# EthernetPHY.net
KiCad netlist of a schematic drawn in Altium Designer
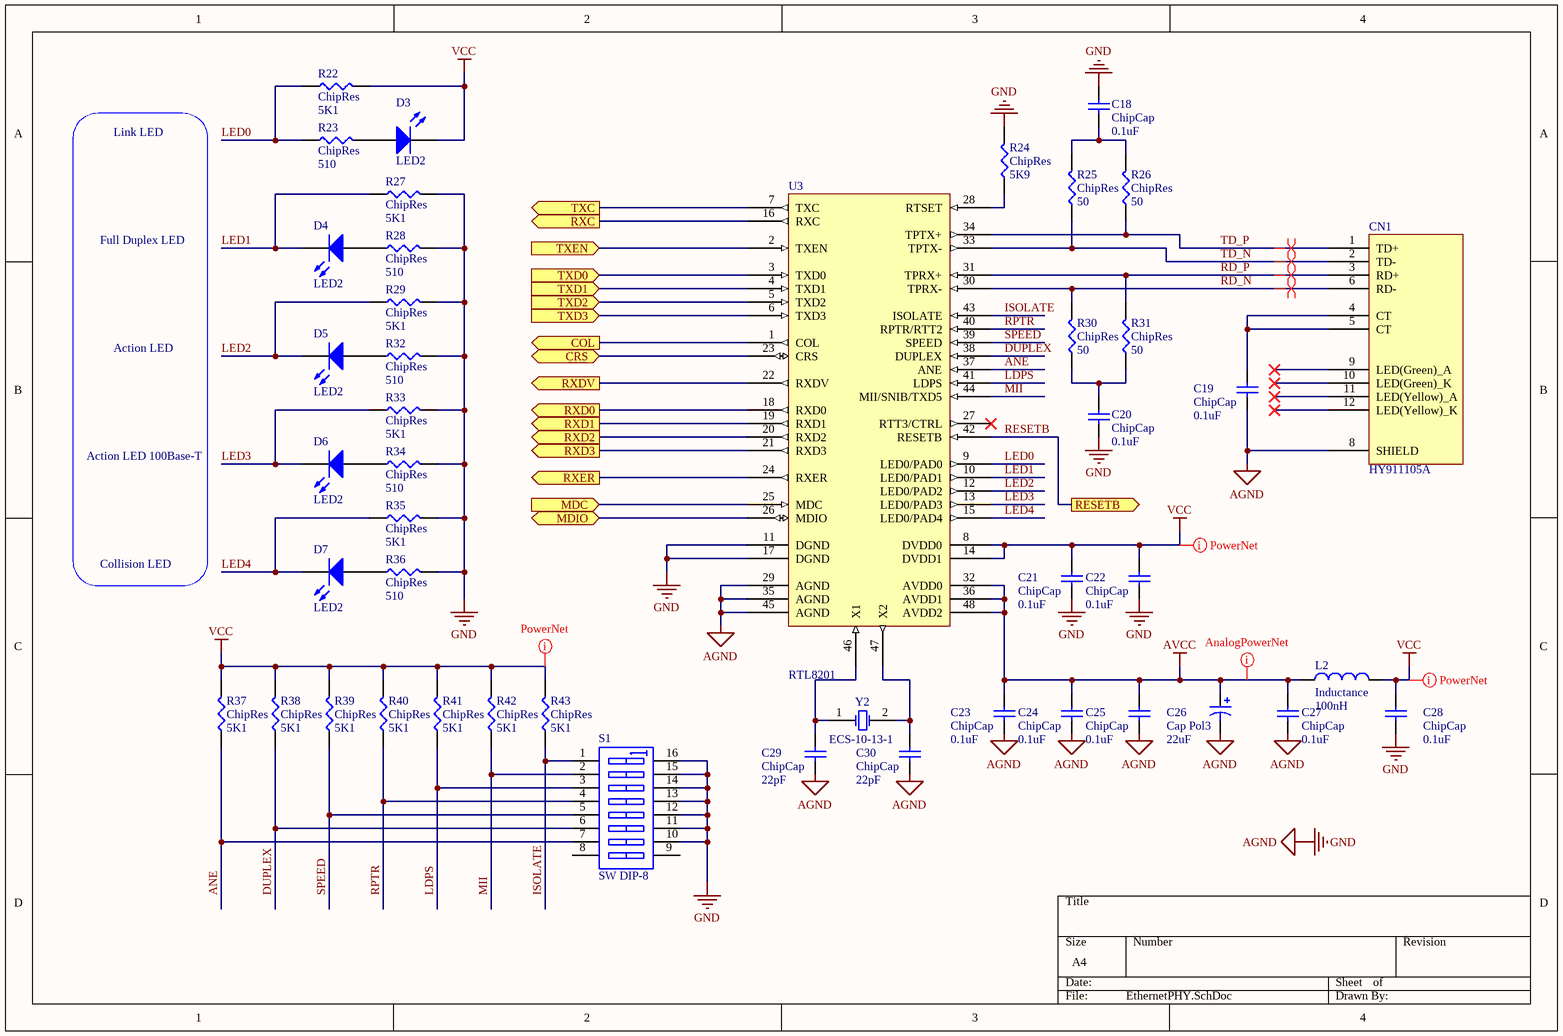
[diagram p0: EthernetPHY.SchDoc]

(export (version "E")
  (design (tool "Eeschema 10.0.6"))
  (components
    (comp (ref "C18")
      (value "ChipCap")
      (footprint "CAP0805")
      (description "Capacitor")
      (fields (field (name "ALTIUM_VALUE") "0.1uF") (field (name "PUBLISHER") "Altium Limited"))
      (libsource (lib "Common Devices") (part "ChipCap"))
    )
    (comp (ref "C19")
      (value "ChipCap")
      (footprint "CAP0805")
      (description "Capacitor")
      (fields (field (name "ALTIUM_VALUE") "0.1uF") (field (name "PUBLISHER") "Altium Limited"))
      (libsource (lib "Common Devices") (part "ChipCap"))
    )
    (comp (ref "C20")
      (value "ChipCap")
      (footprint "CAP0805")
      (description "Capacitor")
      (fields (field (name "ALTIUM_VALUE") "0.1uF") (field (name "PUBLISHER") "Altium Limited"))
      (libsource (lib "Common Devices") (part "ChipCap"))
    )
    (comp (ref "C21")
      (value "ChipCap")
      (footprint "CAP0805")
      (description "Capacitor")
      (fields (field (name "ALTIUM_VALUE") "0.1uF") (field (name "PUBLISHER") "Altium Limited"))
      (libsource (lib "Common Devices") (part "ChipCap"))
    )
    (comp (ref "C22")
      (value "ChipCap")
      (footprint "CAP0805")
      (description "Capacitor")
      (fields (field (name "ALTIUM_VALUE") "0.1uF") (field (name "PUBLISHER") "Altium Limited"))
      (libsource (lib "Common Devices") (part "ChipCap"))
    )
    (comp (ref "C23")
      (value "ChipCap")
      (footprint "CAP0805")
      (description "Capacitor")
      (fields (field (name "ALTIUM_VALUE") "0.1uF") (field (name "PUBLISHER") "Altium Limited"))
      (libsource (lib "Common Devices") (part "ChipCap"))
    )
    (comp (ref "C24")
      (value "ChipCap")
      (footprint "CAP0805")
      (description "Capacitor")
      (fields (field (name "ALTIUM_VALUE") "0.1uF") (field (name "PUBLISHER") "Altium Limited"))
      (libsource (lib "Common Devices") (part "ChipCap"))
    )
    (comp (ref "C25")
      (value "ChipCap")
      (footprint "CAP0805")
      (description "Capacitor")
      (fields (field (name "ALTIUM_VALUE") "0.1uF") (field (name "PUBLISHER") "Altium Limited"))
      (libsource (lib "Common Devices") (part "ChipCap"))
    )
    (comp (ref "C26")
      (value "Cap Pol3")
      (footprint "1812")
      (description "Polarized Capacitor (Surface Mount)")
      (fields (field (name "ALTIUM_VALUE") "22uF") (field (name "PUBLISHER") "Altium Limited"))
      (libsource (lib "Miscellaneous Devices") (part "Cap Pol3"))
    )
    (comp (ref "C27")
      (value "ChipCap")
      (footprint "CAP0805")
      (description "Capacitor")
      (fields (field (name "ALTIUM_VALUE") "0.1uF") (field (name "PUBLISHER") "Altium Limited"))
      (libsource (lib "Common Devices") (part "ChipCap"))
    )
    (comp (ref "C28")
      (value "ChipCap")
      (footprint "CAP0805")
      (description "Capacitor")
      (fields (field (name "ALTIUM_VALUE") "0.1uF") (field (name "PUBLISHER") "Altium Limited"))
      (libsource (lib "Common Devices") (part "ChipCap"))
    )
    (comp (ref "C29")
      (value "ChipCap")
      (footprint "CAP0805")
      (description "Capacitor")
      (fields (field (name "ALTIUM_VALUE") "22pF") (field (name "PUBLISHER") "Altium Limited"))
      (libsource (lib "Common Devices") (part "ChipCap"))
    )
    (comp (ref "C30")
      (value "ChipCap")
      (footprint "CAP0805")
      (description "Capacitor")
      (fields (field (name "ALTIUM_VALUE") "22pF") (field (name "PUBLISHER") "Altium Limited"))
      (libsource (lib "Common Devices") (part "ChipCap"))
    )
    (comp (ref "CN1")
      (value "HY911105A")
      (footprint "HR911105A")
      (libsource (lib "Connectors") (part "HY911105A"))
    )
    (comp (ref "D3")
      (value "LED2")
      (footprint "3.2X1.6X1.1")
      (description "Typical RED, GREEN, YELLOW, AMBER GaAs LED")
      (fields (field (name "PUBLISHER") "Altium Limited"))
      (libsource (lib "Miscellaneous Devices") (part "LED2"))
    )
    (comp (ref "D4")
      (value "LED2")
      (footprint "3.2X1.6X1.1")
      (description "Typical RED, GREEN, YELLOW, AMBER GaAs LED")
      (fields (field (name "PUBLISHER") "Altium Limited"))
      (libsource (lib "Miscellaneous Devices") (part "LED2"))
    )
    (comp (ref "D5")
      (value "LED2")
      (footprint "3.2X1.6X1.1")
      (description "Typical RED, GREEN, YELLOW, AMBER GaAs LED")
      (fields (field (name "PUBLISHER") "Altium Limited"))
      (libsource (lib "Miscellaneous Devices") (part "LED2"))
    )
    (comp (ref "D6")
      (value "LED2")
      (footprint "3.2X1.6X1.1")
      (description "Typical RED, GREEN, YELLOW, AMBER GaAs LED")
      (fields (field (name "PUBLISHER") "Altium Limited"))
      (libsource (lib "Miscellaneous Devices") (part "LED2"))
    )
    (comp (ref "D7")
      (value "LED2")
      (footprint "3.2X1.6X1.1")
      (description "Typical RED, GREEN, YELLOW, AMBER GaAs LED")
      (fields (field (name "PUBLISHER") "Altium Limited"))
      (libsource (lib "Miscellaneous Devices") (part "LED2"))
    )
    (comp (ref "L2")
      (value "Inductance")
      (footprint "CM32")
      (fields (field (name "ALTIUM_VALUE") "100nH"))
      (libsource (lib "Common Devices") (part "ChipInductance"))
    )
    (comp (ref "R22")
      (value "ChipRes")
      (footprint "RES0805")
      (description "Chip resistor")
      (fields (field (name "ALTIUM_VALUE") "5K1"))
      (libsource (lib "Common Devices") (part "ChipRes"))
    )
    (comp (ref "R23")
      (value "ChipRes")
      (footprint "RES0805")
      (description "Chip resistor")
      (fields (field (name "ALTIUM_VALUE") "510"))
      (libsource (lib "Common Devices") (part "ChipRes"))
    )
    (comp (ref "R24")
      (value "ChipRes")
      (footprint "RES0805")
      (description "Chip resistor")
      (fields (field (name "ALTIUM_VALUE") "5K9"))
      (libsource (lib "Common Devices") (part "ChipRes"))
    )
    (comp (ref "R25")
      (value "ChipRes")
      (footprint "RES0805")
      (description "Chip resistor")
      (fields (field (name "ALTIUM_VALUE") "50"))
      (libsource (lib "Common Devices") (part "ChipRes"))
    )
    (comp (ref "R26")
      (value "ChipRes")
      (footprint "RES0805")
      (description "Chip resistor")
      (fields (field (name "ALTIUM_VALUE") "50"))
      (libsource (lib "Common Devices") (part "ChipRes"))
    )
    (comp (ref "R27")
      (value "ChipRes")
      (footprint "RES0805")
      (description "Chip resistor")
      (fields (field (name "ALTIUM_VALUE") "5K1"))
      (libsource (lib "Common Devices") (part "ChipRes"))
    )
    (comp (ref "R28")
      (value "ChipRes")
      (footprint "RES0805")
      (description "Chip resistor")
      (fields (field (name "ALTIUM_VALUE") "510"))
      (libsource (lib "Common Devices") (part "ChipRes"))
    )
    (comp (ref "R29")
      (value "ChipRes")
      (footprint "RES0805")
      (description "Chip resistor")
      (fields (field (name "ALTIUM_VALUE") "5K1"))
      (libsource (lib "Common Devices") (part "ChipRes"))
    )
    (comp (ref "R30")
      (value "ChipRes")
      (footprint "RES0805")
      (description "Chip resistor")
      (fields (field (name "ALTIUM_VALUE") "50"))
      (libsource (lib "Common Devices") (part "ChipRes"))
    )
    (comp (ref "R31")
      (value "ChipRes")
      (footprint "RES0805")
      (description "Chip resistor")
      (fields (field (name "ALTIUM_VALUE") "50"))
      (libsource (lib "Common Devices") (part "ChipRes"))
    )
    (comp (ref "R32")
      (value "ChipRes")
      (footprint "RES0805")
      (description "Chip resistor")
      (fields (field (name "ALTIUM_VALUE") "510"))
      (libsource (lib "Common Devices") (part "ChipRes"))
    )
    (comp (ref "R33")
      (value "ChipRes")
      (footprint "RES0805")
      (description "Chip resistor")
      (fields (field (name "ALTIUM_VALUE") "5K1"))
      (libsource (lib "Common Devices") (part "ChipRes"))
    )
    (comp (ref "R34")
      (value "ChipRes")
      (footprint "RES0805")
      (description "Chip resistor")
      (fields (field (name "ALTIUM_VALUE") "510"))
      (libsource (lib "Common Devices") (part "ChipRes"))
    )
    (comp (ref "R35")
      (value "ChipRes")
      (footprint "RES0805")
      (description "Chip resistor")
      (fields (field (name "ALTIUM_VALUE") "5K1"))
      (libsource (lib "Common Devices") (part "ChipRes"))
    )
    (comp (ref "R36")
      (value "ChipRes")
      (footprint "RES0805")
      (description "Chip resistor")
      (fields (field (name "ALTIUM_VALUE") "510"))
      (libsource (lib "Common Devices") (part "ChipRes"))
    )
    (comp (ref "R37")
      (value "ChipRes")
      (footprint "RES0805")
      (description "Chip resistor")
      (fields (field (name "ALTIUM_VALUE") "5K1"))
      (libsource (lib "Common Devices") (part "ChipRes"))
    )
    (comp (ref "R38")
      (value "ChipRes")
      (footprint "RES0805")
      (description "Chip resistor")
      (fields (field (name "ALTIUM_VALUE") "5K1"))
      (libsource (lib "Common Devices") (part "ChipRes"))
    )
    (comp (ref "R39")
      (value "ChipRes")
      (footprint "RES0805")
      (description "Chip resistor")
      (fields (field (name "ALTIUM_VALUE") "5K1"))
      (libsource (lib "Common Devices") (part "ChipRes"))
    )
    (comp (ref "R40")
      (value "ChipRes")
      (footprint "RES0805")
      (description "Chip resistor")
      (fields (field (name "ALTIUM_VALUE") "5K1"))
      (libsource (lib "Common Devices") (part "ChipRes"))
    )
    (comp (ref "R41")
      (value "ChipRes")
      (footprint "RES0805")
      (description "Chip resistor")
      (fields (field (name "ALTIUM_VALUE") "5K1"))
      (libsource (lib "Common Devices") (part "ChipRes"))
    )
    (comp (ref "R42")
      (value "ChipRes")
      (footprint "RES0805")
      (description "Chip resistor")
      (fields (field (name "ALTIUM_VALUE") "5K1"))
      (libsource (lib "Common Devices") (part "ChipRes"))
    )
    (comp (ref "R43")
      (value "ChipRes")
      (footprint "RES0805")
      (description "Chip resistor")
      (fields (field (name "ALTIUM_VALUE") "5K1"))
      (libsource (lib "Common Devices") (part "ChipRes"))
    )
    (comp (ref "S1")
      (value "SW DIP-8")
      (footprint "DIP_SW_8WAY_SMD")
      (description "DIP Switch, 8 Position, SPST")
      (fields (field (name "PUBLISHER") "Altium Limited"))
      (libsource (lib "Miscellaneous Devices") (part "SW DIP-8"))
    )
    (comp (ref "U3")
      (value "RTL8201")
      (footprint "LQFP48 SOT313-2")
      (libsource (lib "Realtek ETH PHY") (part "RTL8201"))
    )
    (comp (ref "Y2")
      (value "ECS-10-13-1")
      (footprint "HC-49U")
      (description "Crystal Oscillator")
      (fields (field (name "PUBLISHER") "Altium Limited"))
      (libsource (lib "ECS Crystal Oscillator") (part "ECS-10-13-1"))
    )
  )
  (nets
    (net (code "1") (name "/ANE") (class "Default")
      (node (ref "R37") (pin "1") (pintype "passive"))
      (node (ref "S1") (pin "7") (pinfunction "A7_7") (pintype "passive"))
      (node (ref "U3") (pin "37") (pinfunction "ANE_37") (pintype "input"))
    )
    (net (code "2") (name "/COL") (class "Default")
      (node (ref "U3") (pin "1") (pinfunction "COL_1") (pintype "output"))
    )
    (net (code "3") (name "/CRS") (class "Default")
      (node (ref "U3") (pin "23") (pinfunction "CRS_23") (pintype "bidirectional"))
    )
    (net (code "4") (name "/DUPLEX") (class "Default")
      (node (ref "R38") (pin "1") (pintype "passive"))
      (node (ref "S1") (pin "6") (pinfunction "A6_6") (pintype "passive"))
      (node (ref "U3") (pin "38") (pinfunction "DUPLEX_38") (pintype "input"))
    )
    (net (code "5") (name "/ISOLATE") (class "Default")
      (node (ref "R43") (pin "1") (pintype "passive"))
      (node (ref "S1") (pin "1") (pinfunction "A1_1") (pintype "passive"))
      (node (ref "U3") (pin "43") (pinfunction "ISOLATE_43") (pintype "input"))
    )
    (net (code "6") (name "/LDPS") (class "Default")
      (node (ref "R41") (pin "1") (pintype "passive"))
      (node (ref "S1") (pin "3") (pinfunction "A3_3") (pintype "passive"))
      (node (ref "U3") (pin "41") (pinfunction "LDPS_41") (pintype "input"))
    )
    (net (code "7") (name "/LED0") (class "Default")
      (node (ref "R22") (pin "1") (pintype "passive"))
      (node (ref "R23") (pin "1") (pintype "passive"))
      (node (ref "U3") (pin "9") (pinfunction "LED0/PAD0_9") (pintype "output"))
    )
    (net (code "8") (name "/LED1") (class "Default")
      (node (ref "D4") (pin "2") (pinfunction "K_2") (pintype "passive"))
      (node (ref "R27") (pin "1") (pintype "passive"))
      (node (ref "U3") (pin "10") (pinfunction "LED0/PAD1_10") (pintype "output"))
    )
    (net (code "9") (name "/LED2") (class "Default")
      (node (ref "D5") (pin "2") (pinfunction "K_2") (pintype "passive"))
      (node (ref "R29") (pin "1") (pintype "passive"))
      (node (ref "U3") (pin "12") (pinfunction "LED0/PAD2_12") (pintype "output"))
    )
    (net (code "10") (name "/LED3") (class "Default")
      (node (ref "D6") (pin "2") (pinfunction "K_2") (pintype "passive"))
      (node (ref "R33") (pin "1") (pintype "passive"))
      (node (ref "U3") (pin "13") (pinfunction "LED0/PAD3_13") (pintype "output"))
    )
    (net (code "11") (name "/LED4") (class "Default")
      (node (ref "D7") (pin "2") (pinfunction "K_2") (pintype "passive"))
      (node (ref "R35") (pin "1") (pintype "passive"))
      (node (ref "U3") (pin "15") (pinfunction "LED0/PAD4_15") (pintype "output"))
    )
    (net (code "12") (name "/MDC") (class "Default")
      (node (ref "U3") (pin "25") (pinfunction "MDC_25") (pintype "input"))
    )
    (net (code "13") (name "/MDIO") (class "Default")
      (node (ref "U3") (pin "26") (pinfunction "MDIO_26") (pintype "bidirectional"))
    )
    (net (code "14") (name "/MII") (class "Default")
      (node (ref "R42") (pin "1") (pintype "passive"))
      (node (ref "S1") (pin "2") (pinfunction "A2_2") (pintype "passive"))
      (node (ref "U3") (pin "44") (pinfunction "MII/SNIB/TXD5_44") (pintype "input"))
    )
    (net (code "15") (name "/RD_N") (class "Default")
      (node (ref "CN1") (pin "6") (pinfunction "RD-_6") (pintype "passive"))
      (node (ref "R30") (pin "2") (pintype "passive"))
      (node (ref "U3") (pin "30") (pinfunction "TPRX-_30") (pintype "input"))
    )
    (net (code "16") (name "/RD_P") (class "Default")
      (node (ref "CN1") (pin "3") (pinfunction "RD+_3") (pintype "passive"))
      (node (ref "R31") (pin "2") (pintype "passive"))
      (node (ref "U3") (pin "31") (pinfunction "TPRX+_31") (pintype "input"))
    )
    (net (code "17") (name "/RESETB") (class "Default")
      (node (ref "U3") (pin "42") (pinfunction "RESETB_42") (pintype "input"))
    )
    (net (code "18") (name "/RPTR") (class "Default")
      (node (ref "R40") (pin "1") (pintype "passive"))
      (node (ref "S1") (pin "4") (pinfunction "A4_4") (pintype "passive"))
      (node (ref "U3") (pin "40") (pinfunction "RPTR/RTT2_40") (pintype "input"))
    )
    (net (code "19") (name "/RXC") (class "Default")
      (node (ref "U3") (pin "16") (pinfunction "RXC_16") (pintype "output"))
    )
    (net (code "20") (name "/RXD0") (class "Default")
      (node (ref "U3") (pin "18") (pinfunction "RXD0_18") (pintype "output"))
    )
    (net (code "21") (name "/RXD1") (class "Default")
      (node (ref "U3") (pin "19") (pinfunction "RXD1_19") (pintype "output"))
    )
    (net (code "22") (name "/RXD2") (class "Default")
      (node (ref "U3") (pin "20") (pinfunction "RXD2_20") (pintype "output"))
    )
    (net (code "23") (name "/RXD3") (class "Default")
      (node (ref "U3") (pin "21") (pinfunction "RXD3_21") (pintype "output"))
    )
    (net (code "24") (name "/RXDV") (class "Default")
      (node (ref "U3") (pin "22") (pinfunction "RXDV_22") (pintype "output"))
    )
    (net (code "25") (name "/RXER") (class "Default")
      (node (ref "U3") (pin "24") (pinfunction "RXER_24") (pintype "output"))
    )
    (net (code "26") (name "/SPEED") (class "Default")
      (node (ref "R39") (pin "1") (pintype "passive"))
      (node (ref "S1") (pin "5") (pinfunction "A5_5") (pintype "passive"))
      (node (ref "U3") (pin "39") (pinfunction "SPEED_39") (pintype "input"))
    )
    (net (code "27") (name "/TD_N") (class "Default")
      (node (ref "CN1") (pin "2") (pinfunction "TD-_2") (pintype "passive"))
      (node (ref "R25") (pin "1") (pintype "passive"))
      (node (ref "U3") (pin "33") (pinfunction "TPTX-_33") (pintype "output"))
    )
    (net (code "28") (name "/TD_P") (class "Default")
      (node (ref "CN1") (pin "1") (pinfunction "TD+_1") (pintype "passive"))
      (node (ref "R26") (pin "1") (pintype "passive"))
      (node (ref "U3") (pin "34") (pinfunction "TPTX+_34") (pintype "output"))
    )
    (net (code "29") (name "/TXC") (class "Default")
      (node (ref "U3") (pin "7") (pinfunction "TXC_7") (pintype "output"))
    )
    (net (code "30") (name "/TXD0") (class "Default")
      (node (ref "U3") (pin "3") (pinfunction "TXD0_3") (pintype "input"))
    )
    (net (code "31") (name "/TXD1") (class "Default")
      (node (ref "U3") (pin "4") (pinfunction "TXD1_4") (pintype "input"))
    )
    (net (code "32") (name "/TXD2") (class "Default")
      (node (ref "U3") (pin "5") (pinfunction "TXD2_5") (pintype "input"))
    )
    (net (code "33") (name "/TXD3") (class "Default")
      (node (ref "U3") (pin "6") (pinfunction "TXD3_6") (pintype "input"))
    )
    (net (code "34") (name "/TXEN") (class "Default")
      (node (ref "U3") (pin "2") (pinfunction "TXEN_2") (pintype "input"))
    )
    (net (code "35") (name "AGND") (class "Default")
      (node (ref "C18") (pin "2") (pinfunction "2_2") (pintype "passive"))
      (node (ref "C19") (pin "1") (pinfunction "1_1") (pintype "passive"))
      (node (ref "C20") (pin "1") (pinfunction "1_1") (pintype "passive"))
      (node (ref "C21") (pin "1") (pinfunction "1_1") (pintype "passive"))
      (node (ref "C22") (pin "1") (pinfunction "1_1") (pintype "passive"))
      (node (ref "C23") (pin "1") (pinfunction "1_1") (pintype "passive"))
      (node (ref "C24") (pin "1") (pinfunction "1_1") (pintype "passive"))
      (node (ref "C25") (pin "1") (pinfunction "1_1") (pintype "passive"))
      (node (ref "C26") (pin "2") (pinfunction "2_2") (pintype "passive"))
      (node (ref "C27") (pin "1") (pinfunction "1_1") (pintype "passive"))
      (node (ref "C28") (pin "1") (pinfunction "1_1") (pintype "passive"))
      (node (ref "C29") (pin "1") (pinfunction "1_1") (pintype "passive"))
      (node (ref "C30") (pin "1") (pinfunction "1_1") (pintype "passive"))
      (node (ref "CN1") (pin "8") (pinfunction "SHIELD_8") (pintype "passive"))
      (node (ref "R24") (pin "2") (pintype "passive"))
      (node (ref "R27") (pin "2") (pintype "passive"))
      (node (ref "R28") (pin "2") (pintype "passive"))
      (node (ref "R29") (pin "2") (pintype "passive"))
      (node (ref "R32") (pin "2") (pintype "passive"))
      (node (ref "R33") (pin "2") (pintype "passive"))
      (node (ref "R34") (pin "2") (pintype "passive"))
      (node (ref "R35") (pin "2") (pintype "passive"))
      (node (ref "R36") (pin "2") (pintype "passive"))
      (node (ref "S1") (pin "10") (pinfunction "B7_10") (pintype "passive"))
      (node (ref "S1") (pin "11") (pinfunction "B6_11") (pintype "passive"))
      (node (ref "S1") (pin "12") (pinfunction "B5_12") (pintype "passive"))
      (node (ref "S1") (pin "13") (pinfunction "B4_13") (pintype "passive"))
      (node (ref "S1") (pin "14") (pinfunction "B3_14") (pintype "passive"))
      (node (ref "S1") (pin "15") (pinfunction "B2_15") (pintype "passive"))
      (node (ref "S1") (pin "16") (pinfunction "B1_16") (pintype "passive"))
      (node (ref "U3") (pin "11") (pinfunction "DGND_11") (pintype "power_in"))
      (node (ref "U3") (pin "17") (pinfunction "DGND_17") (pintype "power_in"))
      (node (ref "U3") (pin "29") (pinfunction "AGND_29") (pintype "power_in"))
      (node (ref "U3") (pin "35") (pinfunction "AGND_35") (pintype "power_in"))
      (node (ref "U3") (pin "45") (pinfunction "AGND_45") (pintype "power_in"))
    )
    (net (code "36") (name "AVCC") (class "Default")
      (node (ref "C23") (pin "2") (pinfunction "2_2") (pintype "passive"))
      (node (ref "C24") (pin "2") (pinfunction "2_2") (pintype "passive"))
      (node (ref "C25") (pin "2") (pinfunction "2_2") (pintype "passive"))
      (node (ref "C26") (pin "1") (pinfunction "1_1") (pintype "passive"))
      (node (ref "C27") (pin "2") (pinfunction "2_2") (pintype "passive"))
      (node (ref "L2") (pin "2") (pintype "passive"))
      (node (ref "U3") (pin "32") (pinfunction "AVDD0_32") (pintype "power_in"))
      (node (ref "U3") (pin "36") (pinfunction "AVDD1_36") (pintype "power_in"))
      (node (ref "U3") (pin "48") (pinfunction "AVDD2_48") (pintype "power_in"))
    )
    (net (code "37") (name "Net-(C18-Pad1)") (class "Default")
      (node (ref "C18") (pin "1") (pinfunction "1_1") (pintype "passive"))
      (node (ref "R25") (pin "2") (pintype "passive"))
      (node (ref "R26") (pin "2") (pintype "passive"))
    )
    (net (code "38") (name "Net-(C19-Pad2)") (class "Default")
      (node (ref "C19") (pin "2") (pinfunction "2_2") (pintype "passive"))
      (node (ref "CN1") (pin "4") (pinfunction "CT_4") (pintype "passive"))
      (node (ref "CN1") (pin "5") (pinfunction "CT_5") (pintype "passive"))
    )
    (net (code "39") (name "Net-(C20-Pad2)") (class "Default")
      (node (ref "C20") (pin "2") (pinfunction "2_2") (pintype "passive"))
      (node (ref "R30") (pin "1") (pintype "passive"))
      (node (ref "R31") (pin "1") (pintype "passive"))
    )
    (net (code "40") (name "Net-(D3-A)") (class "Default")
      (node (ref "D3") (pin "1") (pinfunction "A_1") (pintype "passive"))
      (node (ref "R23") (pin "2") (pintype "passive"))
    )
    (net (code "41") (name "Net-(D4-A)") (class "Default")
      (node (ref "D4") (pin "1") (pinfunction "A_1") (pintype "passive"))
      (node (ref "R28") (pin "1") (pintype "passive"))
    )
    (net (code "42") (name "Net-(D5-A)") (class "Default")
      (node (ref "D5") (pin "1") (pinfunction "A_1") (pintype "passive"))
      (node (ref "R32") (pin "1") (pintype "passive"))
    )
    (net (code "43") (name "Net-(D6-A)") (class "Default")
      (node (ref "D6") (pin "1") (pinfunction "A_1") (pintype "passive"))
      (node (ref "R34") (pin "1") (pintype "passive"))
    )
    (net (code "44") (name "Net-(D7-A)") (class "Default")
      (node (ref "D7") (pin "1") (pinfunction "A_1") (pintype "passive"))
      (node (ref "R36") (pin "1") (pintype "passive"))
    )
    (net (code "45") (name "Net-(U3-RTSET)") (class "Default")
      (node (ref "R24") (pin "1") (pintype "passive"))
      (node (ref "U3") (pin "28") (pinfunction "RTSET_28") (pintype "input"))
    )
    (net (code "46") (name "Net-(U3-X1)") (class "Default")
      (node (ref "C29") (pin "2") (pinfunction "2_2") (pintype "passive"))
      (node (ref "U3") (pin "46") (pinfunction "X1_46") (pintype "input"))
      (node (ref "Y2") (pin "1") (pinfunction "OSC1_1") (pintype "passive"))
    )
    (net (code "47") (name "Net-(U3-X2)") (class "Default")
      (node (ref "C30") (pin "2") (pinfunction "2_2") (pintype "passive"))
      (node (ref "U3") (pin "47") (pinfunction "X2_47") (pintype "output"))
      (node (ref "Y2") (pin "2") (pinfunction "OSC2_2") (pintype "passive"))
    )
    (net (code "48") (name "VCC") (class "Default")
      (node (ref "C21") (pin "2") (pinfunction "2_2") (pintype "passive"))
      (node (ref "C22") (pin "2") (pinfunction "2_2") (pintype "passive"))
      (node (ref "C28") (pin "2") (pinfunction "2_2") (pintype "passive"))
      (node (ref "D3") (pin "2") (pinfunction "K_2") (pintype "passive"))
      (node (ref "L2") (pin "1") (pintype "passive"))
      (node (ref "R22") (pin "2") (pintype "passive"))
      (node (ref "R37") (pin "2") (pintype "passive"))
      (node (ref "R38") (pin "2") (pintype "passive"))
      (node (ref "R39") (pin "2") (pintype "passive"))
      (node (ref "R40") (pin "2") (pintype "passive"))
      (node (ref "R41") (pin "2") (pintype "passive"))
      (node (ref "R42") (pin "2") (pintype "passive"))
      (node (ref "R43") (pin "2") (pintype "passive"))
      (node (ref "U3") (pin "14") (pinfunction "DVDD1_14") (pintype "power_in"))
      (node (ref "U3") (pin "8") (pinfunction "DVDD0_8") (pintype "power_in"))
    )
    (net (code "49") (name "unconnected-(CN1-LED(Green)_A-Pad9)") (class "Default")
      (node (ref "CN1") (pin "9") (pinfunction "LED(Green)_A_9") (pintype "passive+no_connect"))
    )
    (net (code "50") (name "unconnected-(CN1-LED(Green)_K-Pad10)") (class "Default")
      (node (ref "CN1") (pin "10") (pinfunction "LED(Green)_K_10") (pintype "passive+no_connect"))
    )
    (net (code "51") (name "unconnected-(CN1-LED(Yellow)_A-Pad11)") (class "Default")
      (node (ref "CN1") (pin "11") (pinfunction "LED(Yellow)_A_11") (pintype "passive+no_connect"))
    )
    (net (code "52") (name "unconnected-(CN1-LED(Yellow)_K-Pad12)") (class "Default")
      (node (ref "CN1") (pin "12") (pinfunction "LED(Yellow)_K_12") (pintype "passive+no_connect"))
    )
    (net (code "53") (name "unconnected-(S1-A8-Pad8)") (class "Default")
      (node (ref "S1") (pin "8") (pinfunction "A8_8") (pintype "passive"))
    )
    (net (code "54") (name "unconnected-(S1-B8-Pad9)") (class "Default")
      (node (ref "S1") (pin "9") (pinfunction "B8_9") (pintype "passive"))
    )
    (net (code "55") (name "unconnected-(U3-RTT3{slash}CTRL-Pad27)") (class "Default")
      (node (ref "U3") (pin "27") (pinfunction "RTT3/CTRL_27") (pintype "output+no_connect"))
    )
  )
)
